# VDCProtect.net
KiCad netlist of a schematic drawn in Altium Designer
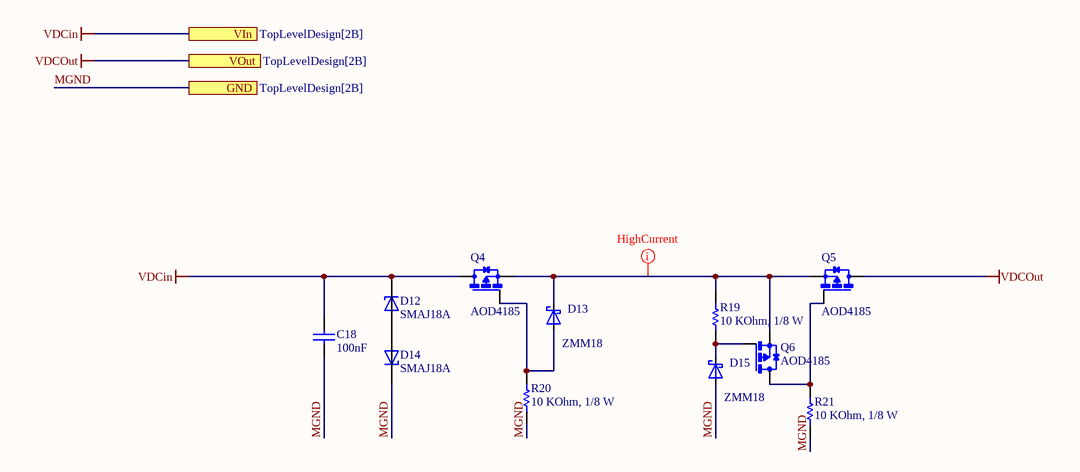
[diagram p0: VDCProtect.SchDoc]

(export (version "E")
  (design (tool "Eeschema 10.0.6"))
  (components
    (comp (ref "C18")
      (value "100nF")
      (footprint "CAP_0805")
      (description "CAP, size 0805, 0.1 nF, 50 VDC")
      (fields
        (field (name "TOLERANCE") "10%")
        (field (name "Comment") "0108051041050")
        (field (name "SOURCE") "Capacitor_0805_10_percent.SchLib")
      )
      (libsource (lib "Tin Tran") (part "0108056841050"))
    )
    (comp (ref "D12")
      (value "SMAJ18A")
      (footprint "DIOM4325X250N")
      (description "400W, 21.1V, 5%, Unidirectional, TVS")
      (fields (field (name "MF") "Taiwan Semiconductor"))
      (libsource (lib "Tin Tran") (part "SMAJ18A"))
    )
    (comp (ref "D13")
      (value "ZMM18")
      (footprint "SOD-80_MiniMELF_Glass")
      (libsource (lib "Tin Tran") (part "Schottky-Diode"))
    )
    (comp (ref "D14")
      (value "SMAJ18A")
      (footprint "DIOM4325X250N")
      (description "400W, 21.1V, 5%, Unidirectional, TVS")
      (fields (field (name "MF") "Taiwan Semiconductor"))
      (libsource (lib "Tin Tran") (part "SMAJ18A"))
    )
    (comp (ref "D15")
      (value "ZMM18")
      (footprint "SOD-80_MiniMELF_Glass")
      (libsource (lib "Tin Tran") (part "Schottky-Diode"))
    )
    (comp (ref "Q4")
      (value "AOD4185")
      (footprint "DPAK")
      (description "P-Channel 40V 40A (Tc) 2.5W (Ta), 62.5W (Tc) Surface Mount TO-252, (D-Pak)")
      (fields (field (name "MF") "Alpha &"))
      (libsource (lib "Tin Tran") (part "AOD4185"))
    )
    (comp (ref "Q5")
      (value "AOD4185")
      (footprint "DPAK")
      (description "P-Channel 40V 40A (Tc) 2.5W (Ta), 62.5W (Tc) Surface Mount TO-252, (D-Pak)")
      (fields (field (name "MF") "Alpha &"))
      (libsource (lib "") (part "AOD4185_1"))
    )
    (comp (ref "Q6")
      (value "AOD4185")
      (footprint "DPAK")
      (description "P-Channel 40V 40A (Tc) 2.5W (Ta), 62.5W (Tc) Surface Mount TO-252, (D-Pak)")
      (fields (field (name "MF") "Alpha &"))
      (libsource (lib "Tin Tran") (part "AOD4185"))
    )
    (comp (ref "R19")
      (value "10 KOhm, 1/8 W")
      (footprint "RESISTOR_0805")
      (description "RES, size 0805, 10 KOhm, 1/8 W")
      (fields (field (name "Comment") "0008051031"))
      (libsource (lib "Tin Tran") (part "0008052035_1"))
    )
    (comp (ref "R20")
      (value "10 KOhm, 1/8 W")
      (footprint "RESISTOR_0805")
      (description "RES, size 0805, 10 KOhm, 1/8 W")
      (fields (field (name "Comment") "0008051031"))
      (libsource (lib "Tin Tran") (part "0008052035_1"))
    )
    (comp (ref "R21")
      (value "10 KOhm, 1/8 W")
      (footprint "RESISTOR_0805")
      (description "RES, size 0805, 10 KOhm, 1/8 W")
      (fields (field (name "Comment") "0008051031"))
      (libsource (lib "Tin Tran") (part "0008052035_1"))
    )
  )
  (nets
    (net (code "1") (name "/MGND") (class "Default")
      (node (ref "C18") (pin "1") (pinfunction "1_1") (pintype "passive"))
      (node (ref "D14") (pin "C") (pinfunction "C_C") (pintype "passive"))
      (node (ref "D15") (pin "A") (pinfunction "A_A") (pintype "passive"))
      (node (ref "R20") (pin "1") (pinfunction "1_1") (pintype "passive"))
      (node (ref "R21") (pin "1") (pinfunction "1_1") (pintype "passive"))
    )
    (net (code "2") (name "Net-(D12-PadA)") (class "Default")
      (node (ref "D12") (pin "A") (pinfunction "A_A") (pintype "passive"))
      (node (ref "D14") (pin "A") (pinfunction "A_A") (pintype "passive"))
    )
    (net (code "3") (name "Net-(Q4-G)") (class "Default")
      (node (ref "D13") (pin "A") (pinfunction "A_A") (pintype "passive"))
      (node (ref "Q4") (pin "1") (pinfunction "G_1") (pintype "passive"))
      (node (ref "R20") (pin "2") (pinfunction "2_2") (pintype "passive"))
    )
    (net (code "4") (name "Net-(Q4-S)") (class "Default")
      (node (ref "D13") (pin "K") (pinfunction "K_K") (pintype "passive"))
      (node (ref "Q4") (pin "3") (pinfunction "S_3") (pintype "passive"))
      (node (ref "Q5") (pin "3") (pinfunction "S_3") (pintype "passive"))
      (node (ref "Q6") (pin "3") (pinfunction "S_3") (pintype "passive"))
      (node (ref "R19") (pin "2") (pinfunction "2_2") (pintype "passive"))
    )
    (net (code "5") (name "Net-(Q5-G)") (class "Default")
      (node (ref "Q5") (pin "1") (pinfunction "G_1") (pintype "passive"))
      (node (ref "Q6") (pin "4") (pinfunction "D_4") (pintype "passive"))
      (node (ref "R21") (pin "2") (pinfunction "2_2") (pintype "passive"))
    )
    (net (code "6") (name "Net-(Q6-G)") (class "Default")
      (node (ref "D15") (pin "K") (pinfunction "K_K") (pintype "passive"))
      (node (ref "Q6") (pin "1") (pinfunction "G_1") (pintype "passive"))
      (node (ref "R19") (pin "1") (pinfunction "1_1") (pintype "passive"))
    )
    (net (code "7") (name "VDCOut") (class "Default")
      (node (ref "Q5") (pin "4") (pinfunction "D_4") (pintype "passive"))
    )
    (net (code "8") (name "VDCin") (class "Default")
      (node (ref "C18") (pin "2") (pinfunction "2_2") (pintype "passive"))
      (node (ref "D12") (pin "C") (pinfunction "C_C") (pintype "passive"))
      (node (ref "Q4") (pin "4") (pinfunction "D_4") (pintype "passive"))
    )
  )
)
